# MCP73833.net
KiCad netlist of a schematic drawn in Altium Designer
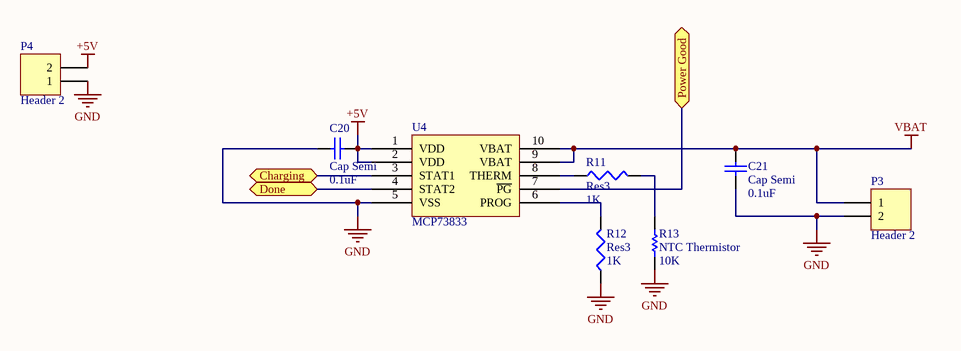
[diagram p0: MCP73833.SchDoc]

(export (version "E")
  (design (tool "Eeschema 10.0.6"))
  (components
    (comp (ref "C20")
      (value "Cap Semi")
      (footprint "1608[0603]")
      (description "Capacitor (Semiconductor SIM Model)")
      (fields (field (name "ALTIUM_VALUE") "0.1uF") (field (name "PUBLISHER") "Altium Limited"))
      (libsource (lib "Miscellaneous Devices") (part "Cap Semi"))
    )
    (comp (ref "C21")
      (value "Cap Semi")
      (footprint "1608[0603]")
      (description "Capacitor (Semiconductor SIM Model)")
      (fields (field (name "ALTIUM_VALUE") "0.1uF") (field (name "PUBLISHER") "Altium Limited"))
      (libsource (lib "Miscellaneous Devices") (part "Cap Semi"))
    )
    (comp (ref "P3")
      (value "Header 2")
      (footprint "JST-PH-2")
      (description "Header, 2-Pin")
      (fields (field (name "PUBLISHER") "Altium Limited"))
      (libsource (lib "Miscellaneous Connectors") (part "Header 2"))
    )
    (comp (ref "P4")
      (value "Header 2")
      (footprint "HDR1X2")
      (description "Header, 2-Pin")
      (fields (field (name "PUBLISHER") "Altium Limited"))
      (libsource (lib "") (part "Header 2_1"))
    )
    (comp (ref "R11")
      (value "Res3")
      (footprint "J1-0603")
      (description "Resistor")
      (fields (field (name "ALTIUM_VALUE") "1K") (field (name "PUBLISHER") "Altium Limited"))
      (libsource (lib "Miscellaneous Devices") (part "Res3"))
    )
    (comp (ref "R12")
      (value "Res3")
      (footprint "J1-0603")
      (description "Resistor")
      (fields (field (name "ALTIUM_VALUE") "1K") (field (name "PUBLISHER") "Altium Limited"))
      (libsource (lib "Miscellaneous Devices") (part "Res3"))
    )
    (comp (ref "R13")
      (value "NTC Thermistor")
      (footprint "AXIAL-0.3")
      (description "Resistor")
      (fields (field (name "ALTIUM_VALUE") "10K") (field (name "PUBLISHER") "Altium Limited"))
      (libsource (lib "Miscellaneous Devices") (part "Res1"))
    )
    (comp (ref "U4")
      (value "MCP73833")
      (footprint "TSSOP50P490X110-10N")
      (libsource (lib "Custom Parts") (part "MCP73833"))
    )
  )
  (nets
    (net (code "1") (name "+5V") (class "Default")
      (node (ref "C20") (pin "1") (pinfunction "1_1") (pintype "passive"))
      (node (ref "P4") (pin "2") (pinfunction "2_2") (pintype "passive"))
      (node (ref "U4") (pin "1") (pinfunction "VDD_1") (pintype "passive"))
      (node (ref "U4") (pin "2") (pinfunction "VDD_2") (pintype "passive"))
    )
    (net (code "2") (name "/Charging") (class "Default")
      (node (ref "U4") (pin "3") (pinfunction "STAT1_3") (pintype "passive"))
    )
    (net (code "3") (name "/Done") (class "Default")
      (node (ref "U4") (pin "4") (pinfunction "STAT2_4") (pintype "passive"))
    )
    (net (code "4") (name "/Power Good") (class "Default")
      (node (ref "U4") (pin "7") (pinfunction "~{PG}_7") (pintype "passive"))
    )
    (net (code "5") (name "GND") (class "Default")
      (node (ref "C20") (pin "2") (pinfunction "2_2") (pintype "passive"))
      (node (ref "C21") (pin "1") (pinfunction "1_1") (pintype "passive"))
      (node (ref "P3") (pin "2") (pinfunction "2_2") (pintype "passive"))
      (node (ref "P4") (pin "1") (pinfunction "1_1") (pintype "passive"))
      (node (ref "R12") (pin "1") (pinfunction "1_1") (pintype "passive"))
      (node (ref "R13") (pin "1") (pinfunction "1_1") (pintype "passive"))
      (node (ref "U4") (pin "5") (pinfunction "VSS_5") (pintype "passive"))
    )
    (net (code "6") (name "Net-(R11-Pad2)") (class "Default")
      (node (ref "R11") (pin "2") (pinfunction "2_2") (pintype "passive"))
      (node (ref "R13") (pin "2") (pinfunction "2_2") (pintype "passive"))
    )
    (net (code "7") (name "Net-(U4-PROG)") (class "Default")
      (node (ref "R12") (pin "2") (pinfunction "2_2") (pintype "passive"))
      (node (ref "U4") (pin "6") (pinfunction "PROG_6") (pintype "passive"))
    )
    (net (code "8") (name "Net-(U4-THERM)") (class "Default")
      (node (ref "R11") (pin "1") (pinfunction "1_1") (pintype "passive"))
      (node (ref "U4") (pin "8") (pinfunction "THERM_8") (pintype "passive"))
    )
    (net (code "9") (name "VBAT") (class "Default")
      (node (ref "C21") (pin "2") (pinfunction "2_2") (pintype "passive"))
      (node (ref "P3") (pin "1") (pinfunction "1_1") (pintype "passive"))
      (node (ref "U4") (pin "10") (pinfunction "VBAT_10") (pintype "passive"))
      (node (ref "U4") (pin "9") (pinfunction "VBAT_9") (pintype "passive"))
    )
  )
)
